# left_panel.net
KiCad netlist of a schematic drawn in Altium Designer
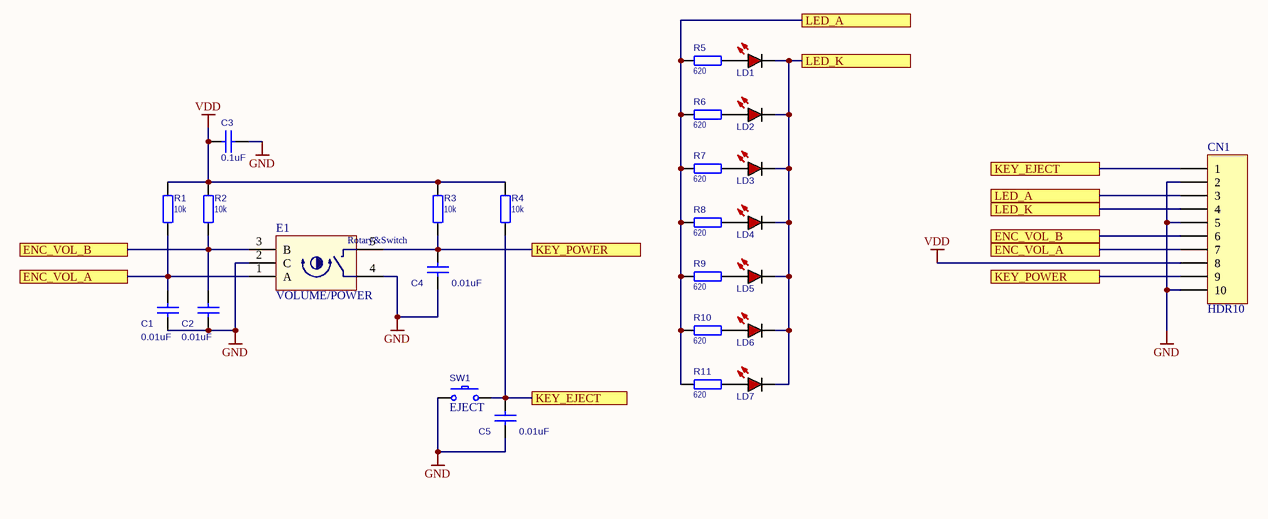
[diagram p0: left_panel.SchDoc]

(export (version "E")
  (design (tool "Eeschema 10.0.6"))
  (components
    (comp (ref "C1")
      (value "0.01uF")
      (footprint "Capacitors:C0603")
      (description "CAP_NPOL")
      (fields (field (name "Comment") "CL10B103KB8NNNC"))
      (libsource (lib "capacitors") (part "CAP_NPOL"))
    )
    (comp (ref "C2")
      (value "0.01uF")
      (footprint "Capacitors:C0603")
      (description "CAP_NPOL")
      (fields (field (name "Comment") "CL10B103KB8NNNC"))
      (libsource (lib "capacitors") (part "CAP_NPOL"))
    )
    (comp (ref "C3")
      (value "0.1uF")
      (footprint "Capacitors:C0603")
      (description "CAP_NPOL")
      (fields (field (name "Comment") "CC0603KRX7R9BB104"))
      (libsource (lib "capacitors") (part "CAP_NPOL"))
    )
    (comp (ref "C4")
      (value "0.01uF")
      (footprint "Capacitors:C0603")
      (description "CAP_NPOL")
      (fields (field (name "Comment") "CL10B103KB8NNNC"))
      (libsource (lib "capacitors") (part "CAP_NPOL"))
    )
    (comp (ref "C5")
      (value "0.01uF")
      (footprint "Capacitors:C0603")
      (description "CAP_NPOL")
      (fields (field (name "Comment") "CL10B103KB8NNNC"))
      (libsource (lib "capacitors") (part "CAP_NPOL"))
    )
    (comp (ref "CN1")
      (value "HDR10")
      (footprint "FPC:10S-0.5SH")
      (description "Header, 10-Pin")
      (fields (field (name "PUBLISHER") "Altium Limited"))
      (libsource (lib "HDR") (part "HDR 10"))
    )
    (comp (ref "E1")
      (value "VOLUME/POWER")
      (footprint "Rotary Encoder")
      (description "ENC_SW")
      (libsource (lib "encoders") (part "ENC_SW"))
    )
    (comp (ref "LD1")
      (value "LED_R")
      (footprint "Leds:LED0805")
      (description "LED Red")
      (libsource (lib "leds") (part "LED_RED"))
    )
    (comp (ref "LD2")
      (value "LED_R")
      (footprint "Leds:LED0805")
      (description "LED Red")
      (libsource (lib "leds") (part "LED_RED"))
    )
    (comp (ref "LD3")
      (value "LED_R")
      (footprint "Leds:LED0805")
      (description "LED Red")
      (libsource (lib "leds") (part "LED_RED"))
    )
    (comp (ref "LD4")
      (value "LED_R")
      (footprint "Leds:LED0805")
      (description "LED Red")
      (libsource (lib "leds") (part "LED_RED"))
    )
    (comp (ref "LD5")
      (value "LED_R")
      (footprint "Leds:LED0805")
      (description "LED Red")
      (libsource (lib "leds") (part "LED_RED"))
    )
    (comp (ref "LD6")
      (value "LED_R")
      (footprint "Leds:LED0805")
      (description "LED Red")
      (libsource (lib "leds") (part "LED_RED"))
    )
    (comp (ref "LD7")
      (value "LED_R")
      (footprint "Leds:LED0805")
      (description "LED Red")
      (libsource (lib "leds") (part "LED_RED"))
    )
    (comp (ref "R1")
      (value "10k")
      (footprint "R0603")
      (description "RES")
      (libsource (lib "resistors") (part "RESISTOR"))
    )
    (comp (ref "R2")
      (value "10k")
      (footprint "R0603")
      (description "RES")
      (libsource (lib "resistors") (part "RESISTOR"))
    )
    (comp (ref "R3")
      (value "10k")
      (footprint "R0603")
      (description "RES")
      (libsource (lib "resistors") (part "RESISTOR"))
    )
    (comp (ref "R4")
      (value "10k")
      (footprint "R0603")
      (description "RES")
      (libsource (lib "resistors") (part "RESISTOR"))
    )
    (comp (ref "R5")
      (value "620")
      (footprint "R0603")
      (description "RES")
      (libsource (lib "resistors") (part "RESISTOR"))
    )
    (comp (ref "R6")
      (value "620")
      (footprint "R0603")
      (description "RES")
      (libsource (lib "resistors") (part "RESISTOR"))
    )
    (comp (ref "R7")
      (value "620")
      (footprint "R0603")
      (description "RES")
      (libsource (lib "resistors") (part "RESISTOR"))
    )
    (comp (ref "R8")
      (value "620")
      (footprint "R0603")
      (description "RES")
      (libsource (lib "resistors") (part "RESISTOR"))
    )
    (comp (ref "R9")
      (value "620")
      (footprint "R0603")
      (description "RES")
      (libsource (lib "resistors") (part "RESISTOR"))
    )
    (comp (ref "R10")
      (value "620")
      (footprint "R0603")
      (description "RES")
      (libsource (lib "resistors") (part "RESISTOR"))
    )
    (comp (ref "R11")
      (value "620")
      (footprint "R0603")
      (description "RES")
      (libsource (lib "resistors") (part "RESISTOR"))
    )
    (comp (ref "SW1")
      (value "EJECT")
      (footprint "Buttons:6X6-SMT-2PIN")
      (description "Microswitches, DTSMB-3 series")
      (libsource (lib "SW-TACT-2PIN") (part "SW tact 2-pin"))
    )
  )
  (nets
    (net (code "1") (name "/ENC_VOL_A") (class "Default")
      (node (ref "C1") (pin "2") (pinfunction "2_2") (pintype "passive"))
      (node (ref "CN1") (pin "7") (pinfunction "7_7") (pintype "passive"))
      (node (ref "E1") (pin "1") (pinfunction "A_1") (pintype "passive"))
      (node (ref "R1") (pin "1") (pinfunction "1_1") (pintype "passive"))
    )
    (net (code "2") (name "/ENC_VOL_B") (class "Default")
      (node (ref "C2") (pin "2") (pinfunction "2_2") (pintype "passive"))
      (node (ref "CN1") (pin "6") (pinfunction "6_6") (pintype "passive"))
      (node (ref "E1") (pin "3") (pinfunction "B_3") (pintype "passive"))
      (node (ref "R2") (pin "2") (pinfunction "2_2") (pintype "passive"))
    )
    (net (code "3") (name "/KEY_EJECT") (class "Default")
      (node (ref "C5") (pin "2") (pinfunction "2_2") (pintype "passive"))
      (node (ref "CN1") (pin "1") (pinfunction "1_1") (pintype "passive"))
      (node (ref "R4") (pin "1") (pinfunction "1_1") (pintype "passive"))
      (node (ref "SW1") (pin "2") (pintype "passive"))
    )
    (net (code "4") (name "/KEY_POWER") (class "Default")
      (node (ref "C4") (pin "2") (pinfunction "2_2") (pintype "passive"))
      (node (ref "CN1") (pin "9") (pinfunction "9_9") (pintype "passive"))
      (node (ref "E1") (pin "5") (pinfunction "SW_5") (pintype "passive"))
      (node (ref "R3") (pin "1") (pinfunction "1_1") (pintype "passive"))
    )
    (net (code "5") (name "/LED_A") (class "Default")
      (node (ref "CN1") (pin "3") (pinfunction "3_3") (pintype "passive"))
      (node (ref "R10") (pin "1") (pinfunction "1_1") (pintype "passive"))
      (node (ref "R11") (pin "1") (pinfunction "1_1") (pintype "passive"))
      (node (ref "R5") (pin "1") (pinfunction "1_1") (pintype "passive"))
      (node (ref "R6") (pin "1") (pinfunction "1_1") (pintype "passive"))
      (node (ref "R7") (pin "1") (pinfunction "1_1") (pintype "passive"))
      (node (ref "R8") (pin "1") (pinfunction "1_1") (pintype "passive"))
      (node (ref "R9") (pin "1") (pinfunction "1_1") (pintype "passive"))
    )
    (net (code "6") (name "/LED_K") (class "Default")
      (node (ref "CN1") (pin "4") (pinfunction "4_4") (pintype "passive"))
      (node (ref "LD1") (pin "1") (pintype "passive"))
      (node (ref "LD2") (pin "1") (pintype "passive"))
      (node (ref "LD3") (pin "1") (pintype "passive"))
      (node (ref "LD4") (pin "1") (pintype "passive"))
      (node (ref "LD5") (pin "1") (pintype "passive"))
      (node (ref "LD6") (pin "1") (pintype "passive"))
      (node (ref "LD7") (pin "1") (pintype "passive"))
    )
    (net (code "7") (name "GND") (class "Default")
      (node (ref "C1") (pin "1") (pinfunction "1_1") (pintype "passive"))
      (node (ref "C2") (pin "1") (pinfunction "1_1") (pintype "passive"))
      (node (ref "C3") (pin "2") (pinfunction "2_2") (pintype "passive"))
      (node (ref "C4") (pin "1") (pinfunction "1_1") (pintype "passive"))
      (node (ref "C5") (pin "1") (pinfunction "1_1") (pintype "passive"))
      (node (ref "CN1") (pin "10") (pinfunction "10_10") (pintype "passive"))
      (node (ref "CN1") (pin "2") (pinfunction "2_2") (pintype "passive"))
      (node (ref "CN1") (pin "5") (pinfunction "5_5") (pintype "passive"))
      (node (ref "E1") (pin "2") (pinfunction "C_2") (pintype "passive"))
      (node (ref "E1") (pin "4") (pinfunction "SW_4") (pintype "passive"))
      (node (ref "SW1") (pin "1") (pintype "passive"))
    )
    (net (code "8") (name "Net-(LD1-Pad2)") (class "Default")
      (node (ref "LD1") (pin "2") (pintype "passive"))
      (node (ref "R5") (pin "2") (pinfunction "2_2") (pintype "passive"))
    )
    (net (code "9") (name "Net-(LD2-Pad2)") (class "Default")
      (node (ref "LD2") (pin "2") (pintype "passive"))
      (node (ref "R6") (pin "2") (pinfunction "2_2") (pintype "passive"))
    )
    (net (code "10") (name "Net-(LD3-Pad2)") (class "Default")
      (node (ref "LD3") (pin "2") (pintype "passive"))
      (node (ref "R7") (pin "2") (pinfunction "2_2") (pintype "passive"))
    )
    (net (code "11") (name "Net-(LD4-Pad2)") (class "Default")
      (node (ref "LD4") (pin "2") (pintype "passive"))
      (node (ref "R8") (pin "2") (pinfunction "2_2") (pintype "passive"))
    )
    (net (code "12") (name "Net-(LD5-Pad2)") (class "Default")
      (node (ref "LD5") (pin "2") (pintype "passive"))
      (node (ref "R9") (pin "2") (pinfunction "2_2") (pintype "passive"))
    )
    (net (code "13") (name "Net-(LD6-Pad2)") (class "Default")
      (node (ref "LD6") (pin "2") (pintype "passive"))
      (node (ref "R10") (pin "2") (pinfunction "2_2") (pintype "passive"))
    )
    (net (code "14") (name "Net-(LD7-Pad2)") (class "Default")
      (node (ref "LD7") (pin "2") (pintype "passive"))
      (node (ref "R11") (pin "2") (pinfunction "2_2") (pintype "passive"))
    )
    (net (code "15") (name "VDD") (class "Default")
      (node (ref "C3") (pin "1") (pinfunction "1_1") (pintype "passive"))
      (node (ref "CN1") (pin "8") (pinfunction "8_8") (pintype "passive"))
      (node (ref "R1") (pin "2") (pinfunction "2_2") (pintype "passive"))
      (node (ref "R2") (pin "1") (pinfunction "1_1") (pintype "passive"))
      (node (ref "R3") (pin "2") (pinfunction "2_2") (pintype "passive"))
      (node (ref "R4") (pin "2") (pinfunction "2_2") (pintype "passive"))
    )
  )
)
